# ReboostV2_Phase.net
KiCad netlist of a schematic drawn in Altium Designer
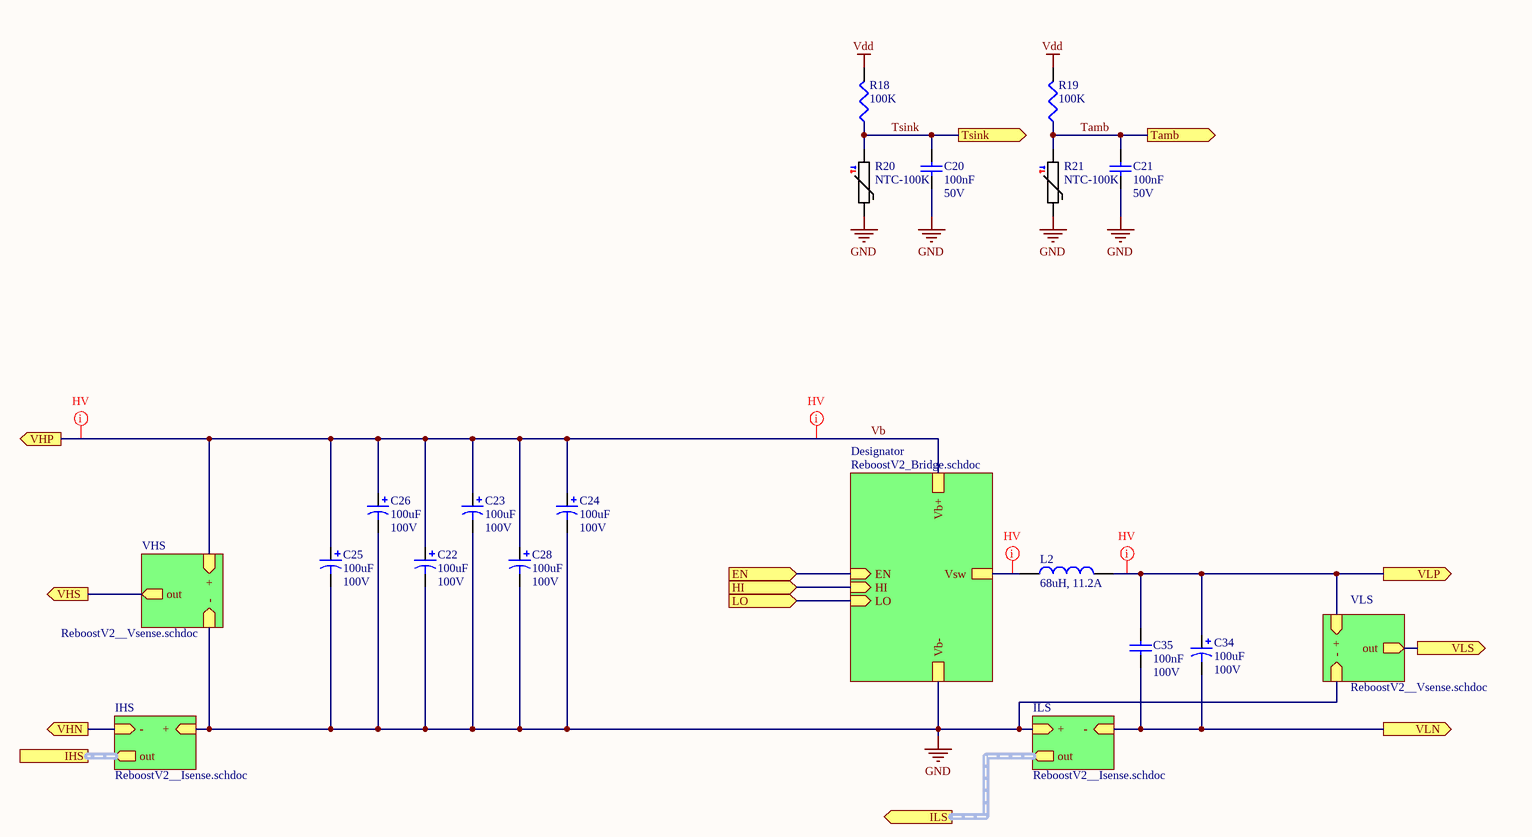
[diagram p0: ReboostV2_Phase.SchDoc]

(export (version "E")
  (design (tool "Eeschema 10.0.6"))
  (components
    (comp (ref "C20")
      (value "100nF")
      (footprint "C0603")
      (description "Capacitor, 100nF, 50V, X7R")
      (fields (field (name "VOLTAGE RATING") "50V"))
      (libsource (lib "AR_Capacitors_Ceramic") (part "100nF/0603/CER/50V"))
    )
    (comp (ref "C21")
      (value "100nF")
      (footprint "C0603")
      (description "Capacitor, 100nF, 50V, X7R")
      (fields (field (name "VOLTAGE RATING") "50V"))
      (libsource (lib "AR_Capacitors_Ceramic") (part "100nF/0603/CER/50V"))
    )
    (comp (ref "C22")
      (value "100uF")
      (footprint "WCAP-ATUL_10x20x5x0.6")
      (description "Aluminum Electrolytic Capacitor, 100uF, 100V")
      (fields (field (name "VOLTAGE RATING") "100V"))
      (libsource (lib "AR_Capacitors_Aluminium") (part "100uF/ALU/100V"))
    )
    (comp (ref "C23")
      (value "100uF")
      (footprint "WCAP-ATUL_10x20x5x0.6")
      (description "Aluminum Electrolytic Capacitor, 100uF, 100V")
      (fields (field (name "VOLTAGE RATING") "100V"))
      (libsource (lib "AR_Capacitors_Aluminium") (part "100uF/ALU/100V"))
    )
    (comp (ref "C24")
      (value "100uF")
      (footprint "WCAP-ATUL_10x20x5x0.6")
      (description "Aluminum Electrolytic Capacitor, 100uF, 100V")
      (fields (field (name "VOLTAGE RATING") "100V"))
      (libsource (lib "AR_Capacitors_Aluminium") (part "100uF/ALU/100V"))
    )
    (comp (ref "C25")
      (value "100uF")
      (footprint "WCAP-ATUL_10x20x5x0.6")
      (description "Aluminum Electrolytic Capacitor, 100uF, 100V")
      (fields (field (name "VOLTAGE RATING") "100V"))
      (libsource (lib "AR_Capacitors_Aluminium") (part "100uF/ALU/100V"))
    )
    (comp (ref "C26")
      (value "100uF")
      (footprint "WCAP-ATUL_10x20x5x0.6")
      (description "Aluminum Electrolytic Capacitor, 100uF, 100V")
      (fields (field (name "VOLTAGE RATING") "100V"))
      (libsource (lib "AR_Capacitors_Aluminium") (part "100uF/ALU/100V"))
    )
    (comp (ref "C28")
      (value "100uF")
      (footprint "WCAP-ATUL_10x20x5x0.6")
      (description "Aluminum Electrolytic Capacitor, 100uF, 100V")
      (fields (field (name "VOLTAGE RATING") "100V"))
      (libsource (lib "AR_Capacitors_Aluminium") (part "100uF/ALU/100V"))
    )
    (comp (ref "C34")
      (value "100uF")
      (footprint "WCAP-ATUL_10x20x5x0.6")
      (description "Aluminum Electrolytic Capacitor, 100uF, 100V")
      (fields (field (name "VOLTAGE RATING") "100V"))
      (libsource (lib "AR_Capacitors_Aluminium") (part "100uF/ALU/100V"))
    )
    (comp (ref "C35")
      (value "100nF")
      (footprint "C-0805")
      (description "Capacitor, 100nF, 100V, X7R")
      (fields (field (name "VOLTAGE RATING") "100V"))
      (libsource (lib "AR_Capacitors_Ceramic") (part "100nF/0805/CER/100V"))
    )
    (comp (ref "L2")
      (value "68uH, 11.2A")
      (footprint "WE-HCF_2920")
      (description "WE-HCF SMT High Current Inductor, size 2920, 68uH, 11.2A, 24.42mOhm")
      (fields
        (field (name "MANUFACTURER") "Wurth Elektronik")
        (field (name "MANUFACTURER PART NUMBER") "74437429203680")
      )
      (libsource (lib "WE-HCF (rev20c)") (part "74437429203680"))
    )
    (comp (ref "R18")
      (value "100K")
      (footprint "0603")
      (description "Resistor, 100K, 1%, 0.063W, 50V, 100PPM, 0603")
      (libsource (lib "AR_Resistors_SMD") (part "100K/0603/0063W/50V"))
    )
    (comp (ref "R19")
      (value "100K")
      (footprint "0603")
      (description "Resistor, 100K, 1%, 0.063W, 50V, 100PPM, 0603")
      (libsource (lib "AR_Resistors_SMD") (part "100K/0603/0063W/50V"))
    )
    (comp (ref "R20")
      (value "NTC-100K")
      (footprint "R0805")
      (description "NTC, 100K, 25°C, 0.5%, 0.210W, 0805")
      (libsource (lib "RCL") (part "NTCS0805E4104JMT"))
    )
    (comp (ref "R21")
      (value "NTC-100K")
      (footprint "R0805")
      (description "NTC, 100K, 25°C, 0.5%, 0.210W, 0805")
      (libsource (lib "RCL") (part "NTCS0805E4104JMT"))
    )
  )
  (nets
    (net (code "6") (name "/Tamb") (class "Default")
      (node (ref "C21") (pin "2") (pinfunction "2_2") (pintype "passive"))
      (node (ref "R19") (pin "1") (pinfunction "1_1") (pintype "passive"))
      (node (ref "R21") (pin "2") (pinfunction "2_2") (pintype "passive"))
    )
    (net (code "7") (name "/Tsink") (class "Default")
      (node (ref "C20") (pin "2") (pinfunction "2_2") (pintype "passive"))
      (node (ref "R18") (pin "1") (pinfunction "1_1") (pintype "passive"))
      (node (ref "R20") (pin "2") (pinfunction "2_2") (pintype "passive"))
    )
    (net (code "10") (name "/VLN") (class "Default")
      (node (ref "C34") (pin "2") (pinfunction "2_2") (pintype "passive"))
      (node (ref "C35") (pin "1") (pinfunction "1_1") (pintype "passive"))
    )
    (net (code "11") (name "/VLP") (class "Default")
      (node (ref "C34") (pin "1") (pinfunction "1_1") (pintype "passive"))
      (node (ref "C35") (pin "2") (pinfunction "2_2") (pintype "passive"))
      (node (ref "L2") (pin "2") (pinfunction "2_2") (pintype "passive"))
    )
    (net (code "13") (name "/Vb") (class "Default")
      (node (ref "C22") (pin "1") (pinfunction "1_1") (pintype "passive"))
      (node (ref "C23") (pin "1") (pinfunction "1_1") (pintype "passive"))
      (node (ref "C24") (pin "1") (pinfunction "1_1") (pintype "passive"))
      (node (ref "C25") (pin "1") (pinfunction "1_1") (pintype "passive"))
      (node (ref "C26") (pin "1") (pinfunction "1_1") (pintype "passive"))
      (node (ref "C28") (pin "1") (pinfunction "1_1") (pintype "passive"))
    )
    (net (code "14") (name "/Vsw") (class "Default")
      (node (ref "L2") (pin "1") (pinfunction "1_1") (pintype "passive"))
    )
    (net (code "15") (name "GND") (class "Default")
      (node (ref "C20") (pin "1") (pinfunction "1_1") (pintype "passive"))
      (node (ref "C21") (pin "1") (pinfunction "1_1") (pintype "passive"))
      (node (ref "C22") (pin "2") (pinfunction "2_2") (pintype "passive"))
      (node (ref "C23") (pin "2") (pinfunction "2_2") (pintype "passive"))
      (node (ref "C24") (pin "2") (pinfunction "2_2") (pintype "passive"))
      (node (ref "C25") (pin "2") (pinfunction "2_2") (pintype "passive"))
      (node (ref "C26") (pin "2") (pinfunction "2_2") (pintype "passive"))
      (node (ref "C28") (pin "2") (pinfunction "2_2") (pintype "passive"))
      (node (ref "R20") (pin "1") (pinfunction "1_1") (pintype "passive"))
      (node (ref "R21") (pin "1") (pinfunction "1_1") (pintype "passive"))
    )
    (net (code "16") (name "Vdd") (class "Default")
      (node (ref "R18") (pin "2") (pinfunction "2_2") (pintype "passive"))
      (node (ref "R19") (pin "2") (pinfunction "2_2") (pintype "passive"))
    )
  )
)
